# 08-DIPSwitches_I2C.net
KiCad netlist of a schematic drawn in Altium Designer
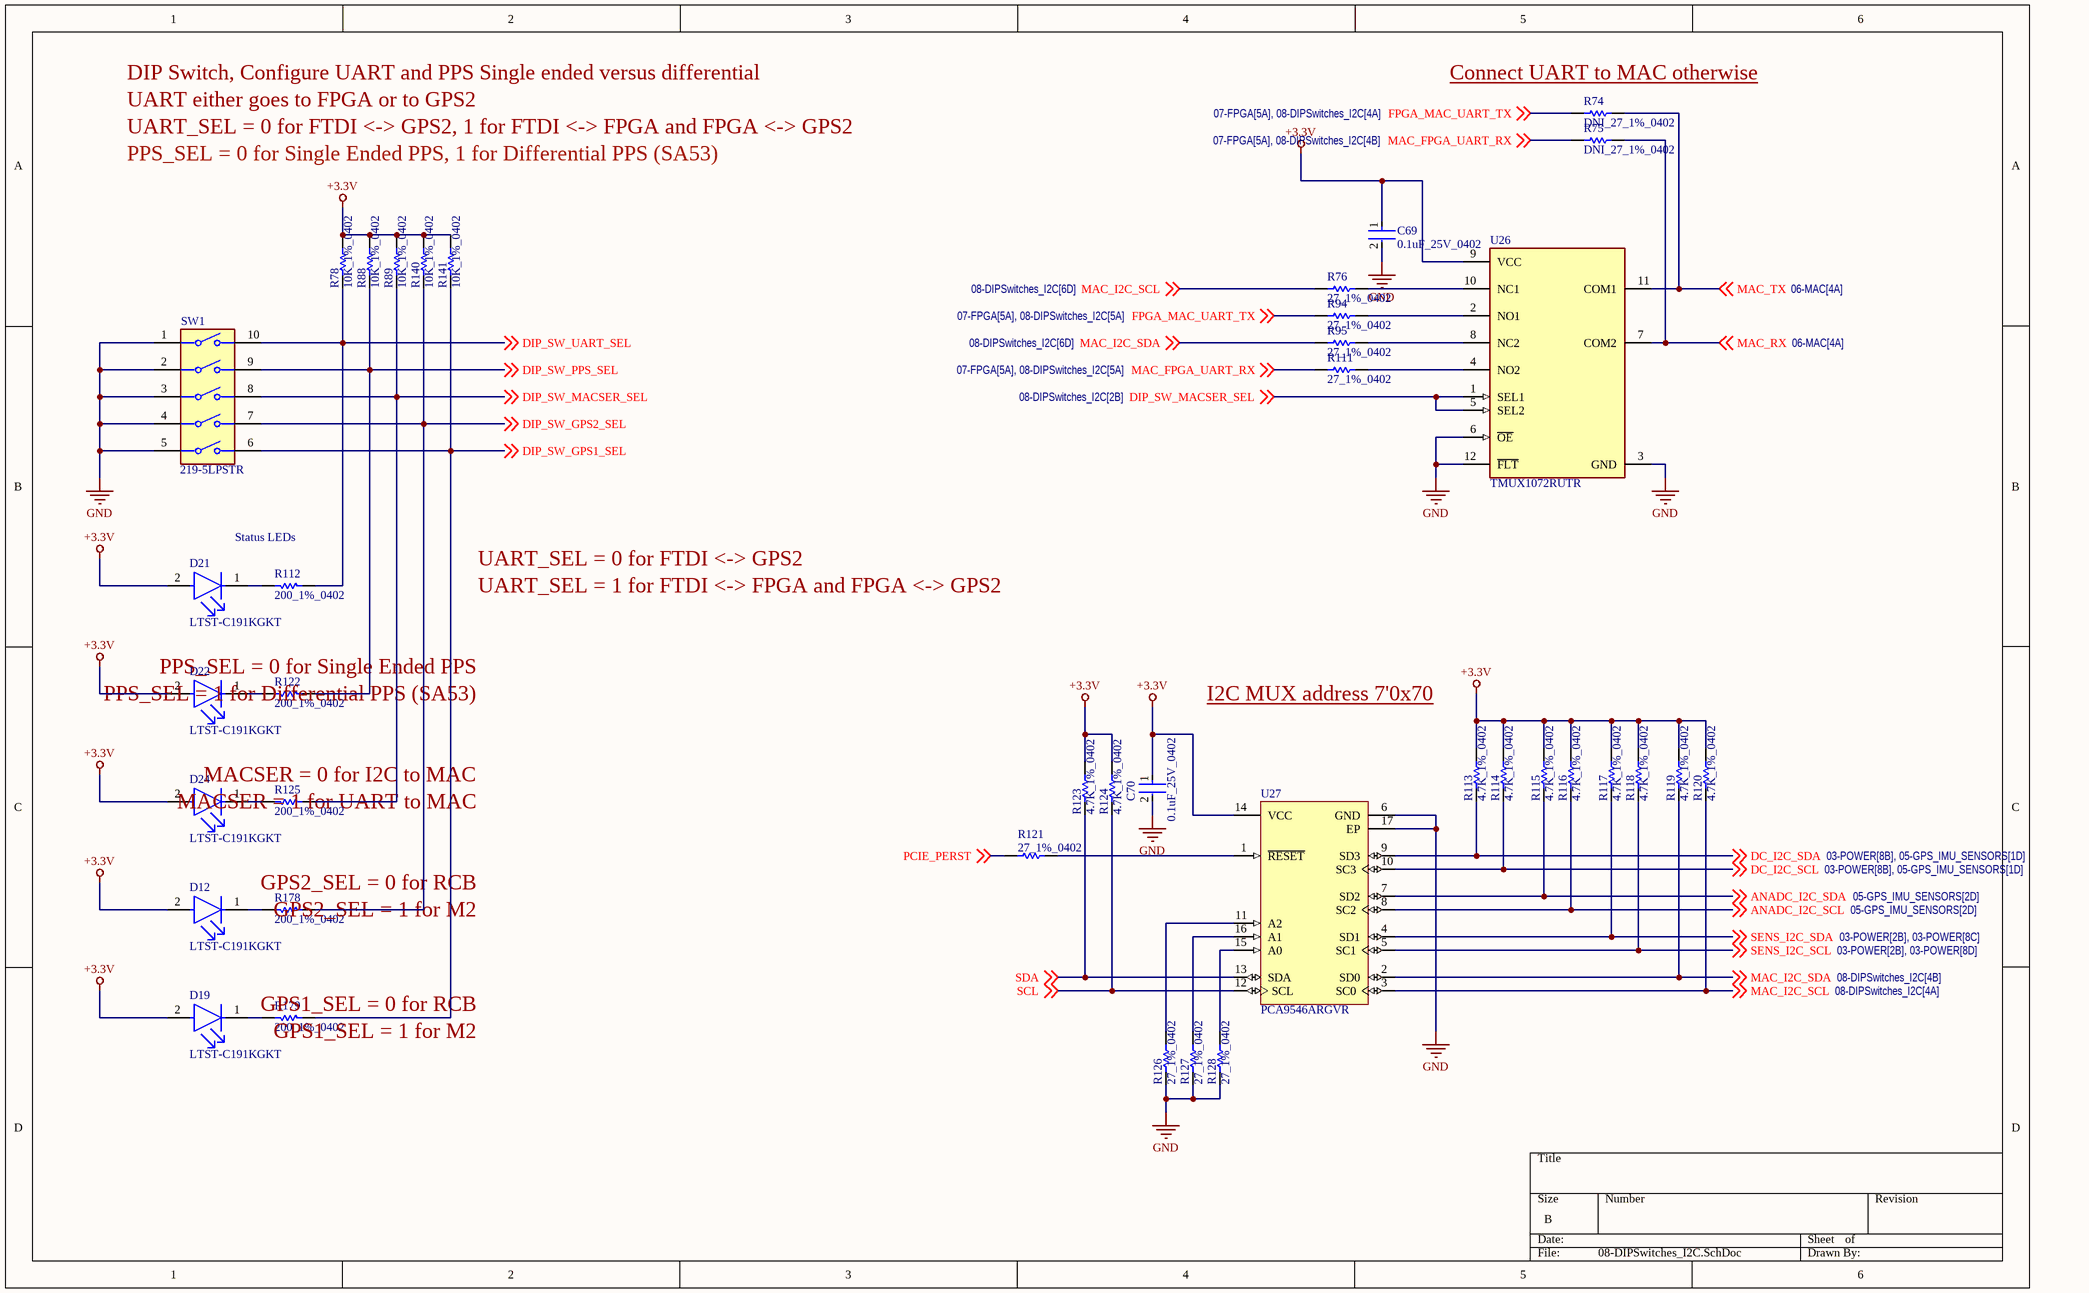
[diagram p0: 08-DIPSwitches_I2C.SchDoc]

(export (version "E")
  (design (tool "Eeschema 10.0.6"))
  (components
    (comp (ref "C69")
      (value "0.1uF_25V_0402")
      (footprint "FP-0402-L_1_0_1-W_0_5_0_1-IPC_C")
      (description "General Purpose Ceramic Capacitor, 0402, 100nF, 10%, X7R, 15%, 25V")
      (fields (field (name "VOLTAGE") "25V") (field (name "TOLERANCE") "10%"))
      (libsource (lib "Altium Content Vault") (part "b4654b650e69147ec39a6b967a45e02"))
    )
    (comp (ref "C70")
      (value "0.1uF_25V_0402")
      (footprint "FP-0402-L_1_0_1-W_0_5_0_1-IPC_C")
      (description "General Purpose Ceramic Capacitor, 0402, 100nF, 10%, X7R, 15%, 25V")
      (fields (field (name "VOLTAGE") "25V") (field (name "TOLERANCE") "10%"))
      (libsource (lib "Altium Content Vault") (part "b4654b650e69147ec39a6b967a45e02"))
    )
    (comp (ref "D12")
      (value "LTST-C191KGKT")
      (footprint "FP-LTST-C191KGKT-MFG")
      (description "LED GREEN CLEAR SMD")
      (libsource (lib "Altium Content Vault") (part "8706943c75ba83719d021d2fdc84c58"))
    )
    (comp (ref "D19")
      (value "LTST-C191KGKT")
      (footprint "FP-LTST-C191KGKT-MFG")
      (description "LED GREEN CLEAR SMD")
      (libsource (lib "Altium Content Vault") (part "8706943c75ba83719d021d2fdc84c58"))
    )
    (comp (ref "D21")
      (value "LTST-C191KGKT")
      (footprint "FP-LTST-C191KGKT-MFG")
      (description "LED GREEN CLEAR SMD")
      (libsource (lib "Altium Content Vault") (part "8706943c75ba83719d021d2fdc84c58"))
    )
    (comp (ref "D22")
      (value "LTST-C191KGKT")
      (footprint "FP-LTST-C191KGKT-MFG")
      (description "LED GREEN CLEAR SMD")
      (libsource (lib "Altium Content Vault") (part "8706943c75ba83719d021d2fdc84c58"))
    )
    (comp (ref "D24")
      (value "LTST-C191KGKT")
      (footprint "FP-LTST-C191KGKT-MFG")
      (description "LED GREEN CLEAR SMD")
      (libsource (lib "Altium Content Vault") (part "8706943c75ba83719d021d2fdc84c58"))
    )
    (comp (ref "R74")
      (value "DNI_27_1%_0402")
      (footprint "RESC1005X40X25NL05T05")
      (fields (field (name "PART NUMBER") "CRCW040227R0FKED") (field (name "MANUFACTURER") "Vishay Dale"))
      (libsource (lib "Altium Content Vault") (part "RES"))
    )
    (comp (ref "R75")
      (value "DNI_27_1%_0402")
      (footprint "RESC1005X40X25NL05T05")
      (fields (field (name "PART NUMBER") "CRCW040227R0FKED") (field (name "MANUFACTURER") "Vishay Dale"))
      (libsource (lib "Altium Content Vault") (part "RES"))
    )
    (comp (ref "R76")
      (value "27_1%_0402")
      (footprint "RESC1005X40X25NL05T05")
      (fields (field (name "PART NUMBER") "CRCW040227R0FKED") (field (name "MANUFACTURER") "Vishay Dale"))
      (libsource (lib "Altium Content Vault") (part "RES"))
    )
    (comp (ref "R78")
      (value "10K_1%_0402")
      (footprint "RESC1005X40X25LL05T10")
      (fields (field (name "PART NUMBER") "RC0402FR-0710KL") (field (name "MANUFACTURER") "Yageo / Phycomp"))
      (libsource (lib "Altium Content Vault") (part "RES"))
    )
    (comp (ref "R88")
      (value "10K_1%_0402")
      (footprint "RESC1005X40X25LL05T10")
      (fields (field (name "PART NUMBER") "RC0402FR-0710KL") (field (name "MANUFACTURER") "Yageo / Phycomp"))
      (libsource (lib "Altium Content Vault") (part "RES"))
    )
    (comp (ref "R89")
      (value "10K_1%_0402")
      (footprint "RESC1005X40X25LL05T10")
      (fields (field (name "PART NUMBER") "RC0402FR-0710KL") (field (name "MANUFACTURER") "Yageo / Phycomp"))
      (libsource (lib "Altium Content Vault") (part "RES"))
    )
    (comp (ref "R94")
      (value "27_1%_0402")
      (footprint "RESC1005X40X25NL05T05")
      (fields (field (name "PART NUMBER") "CRCW040227R0FKED") (field (name "MANUFACTURER") "Vishay Dale"))
      (libsource (lib "Altium Content Vault") (part "RES"))
    )
    (comp (ref "R95")
      (value "27_1%_0402")
      (footprint "RESC1005X40X25NL05T05")
      (fields (field (name "PART NUMBER") "CRCW040227R0FKED") (field (name "MANUFACTURER") "Vishay Dale"))
      (libsource (lib "Altium Content Vault") (part "RES"))
    )
    (comp (ref "R111")
      (value "27_1%_0402")
      (footprint "RESC1005X40X25NL05T05")
      (fields (field (name "PART NUMBER") "CRCW040227R0FKED") (field (name "MANUFACTURER") "Vishay Dale"))
      (libsource (lib "Altium Content Vault") (part "RES"))
    )
    (comp (ref "R112")
      (value "200_1%_0402")
      (footprint "RESC1005X40X25NL05T05")
      (fields (field (name "MANUFACTURER") "Vishay Dale") (field (name "PART NUMBER") "CRCW0402200RFKTD"))
      (libsource (lib "Altium Content Vault") (part "RES"))
    )
    (comp (ref "R113")
      (value "4.7K_1%_0402")
      (footprint "RESC1005X40X25NL10T10")
      (fields (field (name "MANUFACTURER") "Bourns") (field (name "PART NUMBER") "CR0402-FX-4701GLF"))
      (libsource (lib "Altium Content Vault") (part "RES"))
    )
    (comp (ref "R114")
      (value "4.7K_1%_0402")
      (footprint "RESC1005X40X25NL10T10")
      (fields (field (name "MANUFACTURER") "Bourns") (field (name "PART NUMBER") "CR0402-FX-4701GLF"))
      (libsource (lib "Altium Content Vault") (part "RES"))
    )
    (comp (ref "R115")
      (value "4.7K_1%_0402")
      (footprint "RESC1005X40X25NL10T10")
      (fields (field (name "MANUFACTURER") "Bourns") (field (name "PART NUMBER") "CR0402-FX-4701GLF"))
      (libsource (lib "Altium Content Vault") (part "RES"))
    )
    (comp (ref "R116")
      (value "4.7K_1%_0402")
      (footprint "RESC1005X40X25NL10T10")
      (fields (field (name "MANUFACTURER") "Bourns") (field (name "PART NUMBER") "CR0402-FX-4701GLF"))
      (libsource (lib "Altium Content Vault") (part "RES"))
    )
    (comp (ref "R117")
      (value "4.7K_1%_0402")
      (footprint "RESC1005X40X25NL10T10")
      (fields (field (name "MANUFACTURER") "Bourns") (field (name "PART NUMBER") "CR0402-FX-4701GLF"))
      (libsource (lib "Altium Content Vault") (part "RES"))
    )
    (comp (ref "R118")
      (value "4.7K_1%_0402")
      (footprint "RESC1005X40X25NL10T10")
      (fields (field (name "MANUFACTURER") "Bourns") (field (name "PART NUMBER") "CR0402-FX-4701GLF"))
      (libsource (lib "Altium Content Vault") (part "RES"))
    )
    (comp (ref "R119")
      (value "4.7K_1%_0402")
      (footprint "RESC1005X40X25NL10T10")
      (fields (field (name "MANUFACTURER") "Bourns") (field (name "PART NUMBER") "CR0402-FX-4701GLF"))
      (libsource (lib "Altium Content Vault") (part "RES"))
    )
    (comp (ref "R120")
      (value "4.7K_1%_0402")
      (footprint "RESC1005X40X25NL10T10")
      (fields (field (name "MANUFACTURER") "Bourns") (field (name "PART NUMBER") "CR0402-FX-4701GLF"))
      (libsource (lib "Altium Content Vault") (part "RES"))
    )
    (comp (ref "R121")
      (value "27_1%_0402")
      (footprint "RESC1005X40X25NL05T05")
      (fields (field (name "PART NUMBER") "CRCW040227R0FKED") (field (name "MANUFACTURER") "Vishay Dale"))
      (libsource (lib "Altium Content Vault") (part "RES"))
    )
    (comp (ref "R122")
      (value "200_1%_0402")
      (footprint "RESC1005X40X25NL05T05")
      (fields (field (name "MANUFACTURER") "Vishay Dale") (field (name "PART NUMBER") "CRCW0402200RFKTD"))
      (libsource (lib "Altium Content Vault") (part "RES"))
    )
    (comp (ref "R123")
      (value "4.7K_1%_0402")
      (footprint "RESC1005X40X25NL10T10")
      (fields (field (name "MANUFACTURER") "Bourns") (field (name "PART NUMBER") "CR0402-FX-4701GLF"))
      (libsource (lib "Altium Content Vault") (part "RES"))
    )
    (comp (ref "R124")
      (value "4.7K_1%_0402")
      (footprint "RESC1005X40X25NL10T10")
      (fields (field (name "MANUFACTURER") "Bourns") (field (name "PART NUMBER") "CR0402-FX-4701GLF"))
      (libsource (lib "Altium Content Vault") (part "RES"))
    )
    (comp (ref "R125")
      (value "200_1%_0402")
      (footprint "RESC1005X40X25NL05T05")
      (fields (field (name "MANUFACTURER") "Vishay Dale") (field (name "PART NUMBER") "CRCW0402200RFKTD"))
      (libsource (lib "Altium Content Vault") (part "RES"))
    )
    (comp (ref "R126")
      (value "27_1%_0402")
      (footprint "RESC1005X40X25NL05T05")
      (fields (field (name "PART NUMBER") "CRCW040227R0FKED") (field (name "MANUFACTURER") "Vishay Dale"))
      (libsource (lib "Altium Content Vault") (part "RES"))
    )
    (comp (ref "R127")
      (value "27_1%_0402")
      (footprint "RESC1005X40X25NL05T05")
      (fields (field (name "PART NUMBER") "CRCW040227R0FKED") (field (name "MANUFACTURER") "Vishay Dale"))
      (libsource (lib "Altium Content Vault") (part "RES"))
    )
    (comp (ref "R128")
      (value "27_1%_0402")
      (footprint "RESC1005X40X25NL05T05")
      (fields (field (name "PART NUMBER") "CRCW040227R0FKED") (field (name "MANUFACTURER") "Vishay Dale"))
      (libsource (lib "Altium Content Vault") (part "RES"))
    )
    (comp (ref "R140")
      (value "10K_1%_0402")
      (footprint "RESC1005X40X25LL05T10")
      (fields (field (name "PART NUMBER") "RC0402FR-0710KL") (field (name "MANUFACTURER") "Yageo / Phycomp"))
      (libsource (lib "Altium Content Vault") (part "RES"))
    )
    (comp (ref "R141")
      (value "10K_1%_0402")
      (footprint "RESC1005X40X25LL05T10")
      (fields (field (name "PART NUMBER") "RC0402FR-0710KL") (field (name "MANUFACTURER") "Yageo / Phycomp"))
      (libsource (lib "Altium Content Vault") (part "RES"))
    )
    (comp (ref "R178")
      (value "200_1%_0402")
      (footprint "RESC1005X40X25NL05T05")
      (fields (field (name "MANUFACTURER") "Vishay Dale") (field (name "PART NUMBER") "CRCW0402200RFKTD"))
      (libsource (lib "Altium Content Vault") (part "RES"))
    )
    (comp (ref "R179")
      (value "200_1%_0402")
      (footprint "RESC1005X40X25NL05T05")
      (fields (field (name "MANUFACTURER") "Vishay Dale") (field (name "PART NUMBER") "CRCW0402200RFKTD"))
      (libsource (lib "Altium Content Vault") (part "RES"))
    )
    (comp (ref "SW1")
      (value "219-5LPSTR")
      (footprint "FP-219-5LPSTR-MFG")
      (description "SWITCH SLIDE DIP SPST 100MA 20V")
      (libsource (lib "Altium Content Vault") (part "5dac19a08bf10035f124d79214233cd"))
    )
    (comp (ref "U26")
      (value "TMUX1072RUTR")
      (footprint "FP-RUT0012A-MFG")
      (description "IC SWITCH SPDT DUAL 12UQFN")
      (libsource (lib "Altium Content Vault") (part "12a319ab100cd6cfe745e35972674f5"))
    )
    (comp (ref "U27")
      (value "PCA9546ARGVR")
      (footprint "RGV0016A_V")
      (fields (field (name "MANUFACTURER") "Texas Instruments"))
      (libsource (lib "Altium Content Vault") (part "TI-PCA9546A-VQFN_RGV-16"))
    )
  )
  (nets
    (net (code "1") (name "+3.3V") (class "Default")
      (node (ref "C69") (pin "1") (pinfunction "1_1") (pintype "passive"))
      (node (ref "C70") (pin "1") (pinfunction "1_1") (pintype "passive"))
      (node (ref "D12") (pin "2") (pinfunction "A_2") (pintype "passive"))
      (node (ref "D19") (pin "2") (pinfunction "A_2") (pintype "passive"))
      (node (ref "D21") (pin "2") (pinfunction "A_2") (pintype "passive"))
      (node (ref "D22") (pin "2") (pinfunction "A_2") (pintype "passive"))
      (node (ref "D24") (pin "2") (pinfunction "A_2") (pintype "passive"))
      (node (ref "R113") (pin "2") (pinfunction "2_2") (pintype "passive"))
      (node (ref "R114") (pin "2") (pinfunction "2_2") (pintype "passive"))
      (node (ref "R115") (pin "2") (pinfunction "2_2") (pintype "passive"))
      (node (ref "R116") (pin "2") (pinfunction "2_2") (pintype "passive"))
      (node (ref "R117") (pin "2") (pinfunction "2_2") (pintype "passive"))
      (node (ref "R118") (pin "2") (pinfunction "2_2") (pintype "passive"))
      (node (ref "R119") (pin "2") (pinfunction "2_2") (pintype "passive"))
      (node (ref "R120") (pin "2") (pinfunction "2_2") (pintype "passive"))
      (node (ref "R123") (pin "2") (pinfunction "2_2") (pintype "passive"))
      (node (ref "R124") (pin "2") (pinfunction "2_2") (pintype "passive"))
      (node (ref "R140") (pin "1") (pinfunction "1_1") (pintype "passive"))
      (node (ref "R141") (pin "1") (pinfunction "1_1") (pintype "passive"))
      (node (ref "R78") (pin "1") (pinfunction "1_1") (pintype "passive"))
      (node (ref "R88") (pin "1") (pinfunction "1_1") (pintype "passive"))
      (node (ref "R89") (pin "1") (pinfunction "1_1") (pintype "passive"))
      (node (ref "U26") (pin "9") (pinfunction "VCC_9") (pintype "power_in"))
      (node (ref "U27") (pin "14") (pinfunction "VCC_14") (pintype "power_in"))
    )
    (net (code "2") (name "ANADC_I2C_SCL") (class "Default")
      (node (ref "R116") (pin "1") (pinfunction "1_1") (pintype "passive"))
      (node (ref "U27") (pin "8") (pinfunction "SC2_8") (pintype "bidirectional"))
    )
    (net (code "3") (name "ANADC_I2C_SDA") (class "Default")
      (node (ref "R115") (pin "1") (pinfunction "1_1") (pintype "passive"))
      (node (ref "U27") (pin "7") (pinfunction "SD2_7") (pintype "bidirectional"))
    )
    (net (code "4") (name "DC_I2C_SCL") (class "Default")
      (node (ref "R114") (pin "1") (pinfunction "1_1") (pintype "passive"))
      (node (ref "U27") (pin "10") (pinfunction "SC3_10") (pintype "bidirectional"))
    )
    (net (code "5") (name "DC_I2C_SDA") (class "Default")
      (node (ref "R113") (pin "1") (pinfunction "1_1") (pintype "passive"))
      (node (ref "U27") (pin "9") (pinfunction "SD3_9") (pintype "bidirectional"))
    )
    (net (code "6") (name "DIP_SW_GPS1_SEL") (class "Default")
      (node (ref "R141") (pin "2") (pinfunction "2_2") (pintype "passive"))
      (node (ref "R179") (pin "2") (pinfunction "2_2") (pintype "passive"))
      (node (ref "SW1") (pin "6") (pinfunction "6_6") (pintype "passive"))
    )
    (net (code "7") (name "DIP_SW_GPS2_SEL") (class "Default")
      (node (ref "R140") (pin "2") (pinfunction "2_2") (pintype "passive"))
      (node (ref "R178") (pin "2") (pinfunction "2_2") (pintype "passive"))
      (node (ref "SW1") (pin "7") (pinfunction "7_7") (pintype "passive"))
    )
    (net (code "8") (name "DIP_SW_MACSER_SEL") (class "Default")
      (node (ref "R125") (pin "2") (pinfunction "2_2") (pintype "passive"))
      (node (ref "R89") (pin "2") (pinfunction "2_2") (pintype "passive"))
      (node (ref "SW1") (pin "8") (pinfunction "8_8") (pintype "passive"))
      (node (ref "U26") (pin "1") (pinfunction "SEL1_1") (pintype "input"))
      (node (ref "U26") (pin "5") (pinfunction "SEL2_5") (pintype "input"))
    )
    (net (code "9") (name "DIP_SW_PPS_SEL") (class "Default")
      (node (ref "R122") (pin "2") (pinfunction "2_2") (pintype "passive"))
      (node (ref "R88") (pin "2") (pinfunction "2_2") (pintype "passive"))
      (node (ref "SW1") (pin "9") (pinfunction "9_9") (pintype "passive"))
    )
    (net (code "10") (name "DIP_SW_UART_SEL") (class "Default")
      (node (ref "R112") (pin "2") (pinfunction "2_2") (pintype "passive"))
      (node (ref "R78") (pin "2") (pinfunction "2_2") (pintype "passive"))
      (node (ref "SW1") (pin "10") (pinfunction "10_10") (pintype "passive"))
    )
    (net (code "11") (name "FPGA_MAC_UART_TX") (class "Default")
      (node (ref "R74") (pin "1") (pinfunction "1_1") (pintype "passive"))
      (node (ref "R94") (pin "1") (pinfunction "1_1") (pintype "passive"))
    )
    (net (code "12") (name "GND") (class "Default")
      (node (ref "C69") (pin "2") (pinfunction "2_2") (pintype "passive"))
      (node (ref "C70") (pin "2") (pinfunction "2_2") (pintype "passive"))
      (node (ref "R126") (pin "1") (pinfunction "1_1") (pintype "passive"))
      (node (ref "R127") (pin "1") (pinfunction "1_1") (pintype "passive"))
      (node (ref "R128") (pin "1") (pinfunction "1_1") (pintype "passive"))
      (node (ref "SW1") (pin "1") (pinfunction "1_1") (pintype "passive"))
      (node (ref "SW1") (pin "2") (pinfunction "2_2") (pintype "passive"))
      (node (ref "SW1") (pin "3") (pinfunction "3_3") (pintype "passive"))
      (node (ref "SW1") (pin "4") (pinfunction "4_4") (pintype "passive"))
      (node (ref "SW1") (pin "5") (pinfunction "5_5") (pintype "passive"))
      (node (ref "U26") (pin "12") (pinfunction "~{FLT}_12") (pintype "open_collector"))
      (node (ref "U26") (pin "3") (pinfunction "GND_3") (pintype "power_in"))
      (node (ref "U26") (pin "6") (pinfunction "~{OE}_6") (pintype "input"))
      (node (ref "U27") (pin "17") (pinfunction "EP_17") (pintype "passive"))
      (node (ref "U27") (pin "6") (pinfunction "GND_6") (pintype "power_in"))
    )
    (net (code "13") (name "MAC_FPGA_UART_RX") (class "Default")
      (node (ref "R111") (pin "1") (pinfunction "1_1") (pintype "passive"))
      (node (ref "R75") (pin "1") (pinfunction "1_1") (pintype "passive"))
    )
    (net (code "14") (name "MAC_I2C_SCL") (class "Default")
      (node (ref "R120") (pin "1") (pinfunction "1_1") (pintype "passive"))
      (node (ref "R76") (pin "1") (pinfunction "1_1") (pintype "passive"))
      (node (ref "U27") (pin "3") (pinfunction "SC0_3") (pintype "bidirectional"))
    )
    (net (code "15") (name "MAC_I2C_SDA") (class "Default")
      (node (ref "R119") (pin "1") (pinfunction "1_1") (pintype "passive"))
      (node (ref "R95") (pin "1") (pinfunction "1_1") (pintype "passive"))
      (node (ref "U27") (pin "2") (pinfunction "SD0_2") (pintype "bidirectional"))
    )
    (net (code "16") (name "MAC_RX") (class "Default")
      (node (ref "R75") (pin "2") (pinfunction "2_2") (pintype "passive"))
      (node (ref "U26") (pin "7") (pinfunction "COM2_7") (pintype "passive"))
    )
    (net (code "17") (name "MAC_TX") (class "Default")
      (node (ref "R74") (pin "2") (pinfunction "2_2") (pintype "passive"))
      (node (ref "U26") (pin "11") (pinfunction "COM1_11") (pintype "passive"))
    )
    (net (code "18") (name "Net-(D12-C)") (class "Default")
      (node (ref "D12") (pin "1") (pinfunction "C_1") (pintype "passive"))
      (node (ref "R178") (pin "1") (pinfunction "1_1") (pintype "passive"))
    )
    (net (code "19") (name "Net-(D19-C)") (class "Default")
      (node (ref "D19") (pin "1") (pinfunction "C_1") (pintype "passive"))
      (node (ref "R179") (pin "1") (pinfunction "1_1") (pintype "passive"))
    )
    (net (code "20") (name "Net-(D21-C)") (class "Default")
      (node (ref "D21") (pin "1") (pinfunction "C_1") (pintype "passive"))
      (node (ref "R112") (pin "1") (pinfunction "1_1") (pintype "passive"))
    )
    (net (code "21") (name "Net-(D22-C)") (class "Default")
      (node (ref "D22") (pin "1") (pinfunction "C_1") (pintype "passive"))
      (node (ref "R122") (pin "1") (pinfunction "1_1") (pintype "passive"))
    )
    (net (code "22") (name "Net-(D24-C)") (class "Default")
      (node (ref "D24") (pin "1") (pinfunction "C_1") (pintype "passive"))
      (node (ref "R125") (pin "1") (pinfunction "1_1") (pintype "passive"))
    )
    (net (code "23") (name "Net-(U26-NC1)") (class "Default")
      (node (ref "R76") (pin "2") (pinfunction "2_2") (pintype "passive"))
      (node (ref "U26") (pin "10") (pinfunction "NC1_10") (pintype "passive"))
    )
    (net (code "24") (name "Net-(U26-NC2)") (class "Default")
      (node (ref "R95") (pin "2") (pinfunction "2_2") (pintype "passive"))
      (node (ref "U26") (pin "8") (pinfunction "NC2_8") (pintype "passive"))
    )
    (net (code "25") (name "Net-(U26-NO1)") (class "Default")
      (node (ref "R94") (pin "2") (pinfunction "2_2") (pintype "passive"))
      (node (ref "U26") (pin "2") (pinfunction "NO1_2") (pintype "passive"))
    )
    (net (code "26") (name "Net-(U26-NO2)") (class "Default")
      (node (ref "R111") (pin "2") (pinfunction "2_2") (pintype "passive"))
      (node (ref "U26") (pin "4") (pinfunction "NO2_4") (pintype "passive"))
    )
    (net (code "27") (name "Net-(U27-A0)") (class "Default")
      (node (ref "R128") (pin "2") (pinfunction "2_2") (pintype "passive"))
      (node (ref "U27") (pin "15") (pinfunction "A0_15") (pintype "input"))
    )
    (net (code "28") (name "Net-(U27-A1)") (class "Default")
      (node (ref "R127") (pin "2") (pinfunction "2_2") (pintype "passive"))
      (node (ref "U27") (pin "16") (pinfunction "A1_16") (pintype "input"))
    )
    (net (code "29") (name "Net-(U27-A2)") (class "Default")
      (node (ref "R126") (pin "2") (pinfunction "2_2") (pintype "passive"))
      (node (ref "U27") (pin "11") (pinfunction "A2_11") (pintype "input"))
    )
    (net (code "30") (name "Net-(U27-~{RESET})") (class "Default")
      (node (ref "R121") (pin "2") (pinfunction "2_2") (pintype "passive"))
      (node (ref "U27") (pin "1") (pinfunction "~{RESET}_1") (pintype "input"))
    )
    (net (code "31") (name "PCIE_PERST") (class "Default")
      (node (ref "R121") (pin "1") (pinfunction "1_1") (pintype "passive"))
    )
    (net (code "32") (name "SCL") (class "Default")
      (node (ref "R124") (pin "1") (pinfunction "1_1") (pintype "passive"))
      (node (ref "U27") (pin "12") (pinfunction "SCL_12") (pintype "bidirectional"))
    )
    (net (code "33") (name "SDA") (class "Default")
      (node (ref "R123") (pin "1") (pinfunction "1_1") (pintype "passive"))
      (node (ref "U27") (pin "13") (pinfunction "SDA_13") (pintype "bidirectional"))
    )
    (net (code "34") (name "SENS_I2C_SCL") (class "Default")
      (node (ref "R118") (pin "1") (pinfunction "1_1") (pintype "passive"))
      (node (ref "U27") (pin "5") (pinfunction "SC1_5") (pintype "bidirectional"))
    )
    (net (code "35") (name "SENS_I2C_SDA") (class "Default")
      (node (ref "R117") (pin "1") (pinfunction "1_1") (pintype "passive"))
      (node (ref "U27") (pin "4") (pinfunction "SD1_4") (pintype "bidirectional"))
    )
  )
)
